# 846-XXXXX_SCH_NEO-M9N_MODULE_2_RECEIVER.net
KiCad netlist of a schematic drawn in Altium Designer
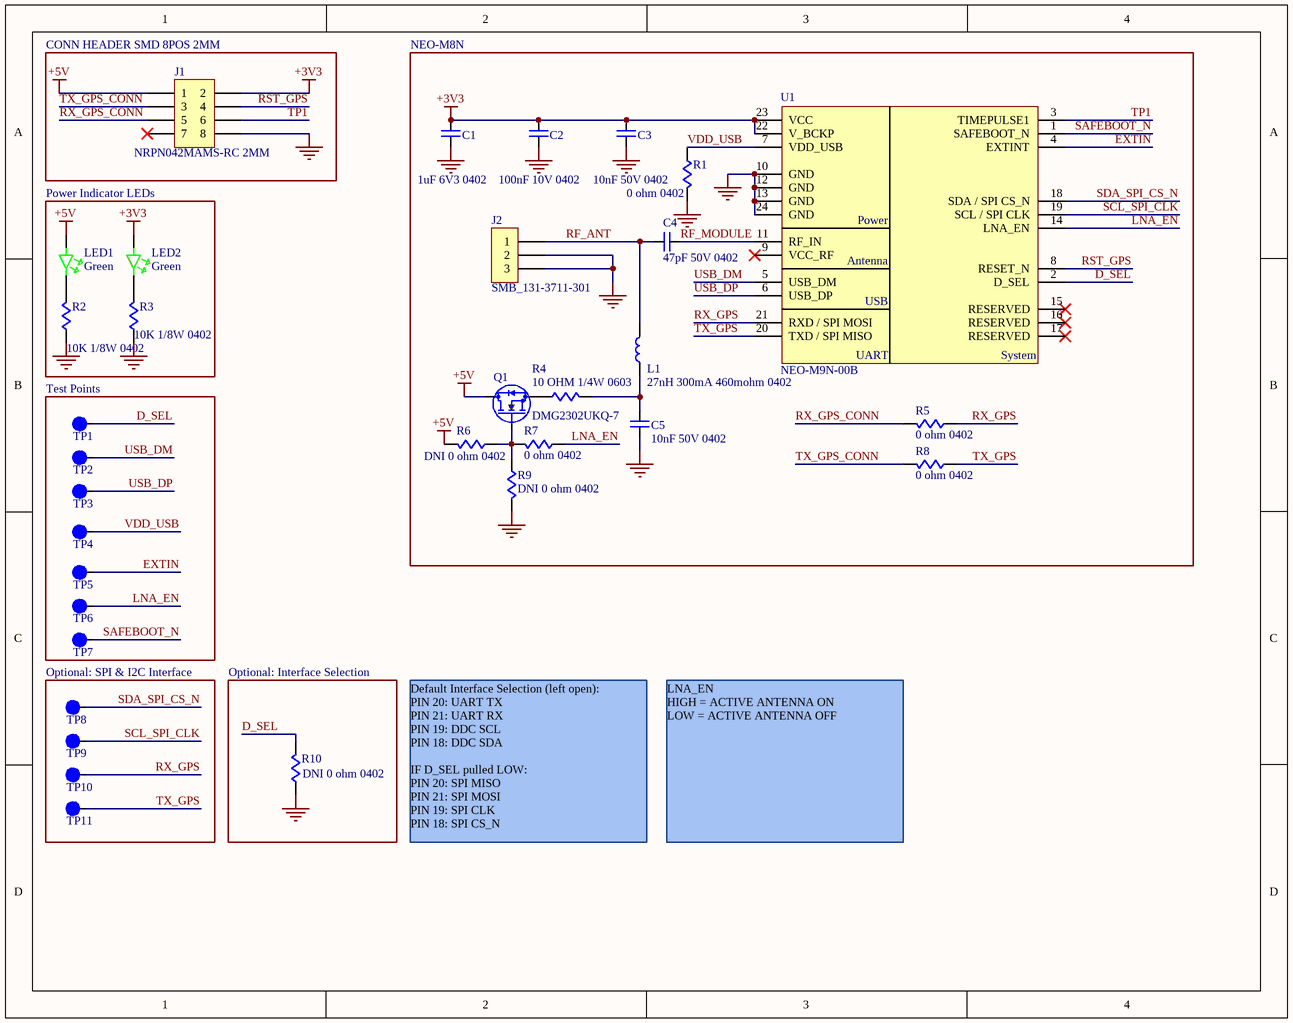
[diagram p0: 846-XXXXX_SCH_NEO-M9N_MODULE_2_RECEIVER.SchDoc]

(export (version "E")
  (design (tool "Eeschema 10.0.6"))
  (components
    (comp (ref "C1")
      (value "1uF 6V3 0402")
      (footprint "c0402")
      (description "0402 1 uF 6.3 V ±10% Tolerance X7R Multilayer Ceramic Capacitor")
      (fields
        (field (name "MANUFACTURER") "Murata")
        (field (name "MANUFACTURER PART NUMBER") "GRM155R70J105KA12J")
      )
      (libsource (lib "MyLibrary") (part "CAP CER 1UF 6.3V X7R 0402"))
    )
    (comp (ref "C2")
      (value "100nF 10V 0402")
      (footprint "c0402")
      (description "CL05 Series 0.1 uF 10 V ±10 % Tolerance X7R SMT Multilayer Ceramic Capacitor")
      (fields
        (field (name "MANUFACTURER") "Samsung")
        (field (name "MANUFACTURER PART NUMBER") "CL05B104KP5NNNC")
      )
      (libsource (lib "MyLibrary") (part "CAP CER 0.1UF 10V X7R 0402"))
    )
    (comp (ref "C3")
      (value "10nF 50V 0402")
      (footprint "c0402")
      (description "CAP CER 10000PF 50V X7R 0402")
      (fields
        (field (name "MANUFACTURER") "Murata")
        (field (name "MANUFACTURER PART NUMBER") "GCM155R71H103KA55D")
      )
      (libsource (lib "MyLibrary") (part "CAP CER 10000PF 50V X7R 0402"))
    )
    (comp (ref "C4")
      (value "47pF 50V 0402")
      (footprint "c0402")
      (description "0402 47 pF 50 V ±5 % Tolerance NP0 SMT Multilayer Ceramic Capacitor")
      (fields
        (field (name "MANUFACTURER") "Yageo")
        (field (name "MANUFACTURER PART NUMBER") "CC0402JRNPO9BN470")
      )
      (libsource (lib "MyLibrary") (part "CAP CER 47PF 50V C0G/NPO 0402"))
    )
    (comp (ref "C5")
      (value "10nF 50V 0402")
      (footprint "c0402")
      (description "CAP CER 10000PF 50V X7R 0402")
      (fields
        (field (name "MANUFACTURER") "Murata")
        (field (name "MANUFACTURER PART NUMBER") "GCM155R71H103KA55D")
      )
      (libsource (lib "MyLibrary") (part "CAP CER 10000PF 50V X7R 0402"))
    )
    (comp (ref "J1")
      (value "NRPN042MAMS-RC 2MM")
      (footprint "CONN_NRPN042MAMS-RC")
      (description "Dual Row 8 Position 2 mm Pitch Surface Mount Header")
      (fields
        (field (name "MANUFACTURER") "Sullins")
        (field (name "MANUFACTURER PART NUMBER") "NRPN042MAMS-RC")
      )
      (libsource (lib "MyLibrary") (part "CONN_NRPN042MAMS-RC"))
    )
    (comp (ref "J2")
      (value "SMB_131-3711-301")
      (footprint "CONN_131-3711-301")
      (description "Rf Coaxial Board Mount Connector")
      (fields
        (field (name "MANUFACTURER") "Bel Cinch")
        (field (name "MANUFACTURER PART NUMBER") "131-3711-301")
      )
      (libsource (lib "MyLibrary") (part "CONN_131-3711-301"))
    )
    (comp (ref "L1")
      (value "27nH 300mA 460mohm 0402")
      (footprint "L0402")
      (description "Inductor RF Chip Multi-Layer 27nH 5% 100MHz 8Q-Factor Air 300mA 460mOhm DCR 0402 Paper T/R")
      (fields
        (field (name "MANUFACTURER") "Murata")
        (field (name "MANUFACTURER PART NUMBER") "LQG15HS27NJ02D")
      )
      (libsource (lib "MyLibrary") (part "FIXED IND 27NH 350MA 460MOHM SMD"))
    )
    (comp (ref "LED1")
      (value "Green")
      (footprint "led0603")
      (description "LED High-Power Uni-Color Green 574nm 2-Pin Chip LED T/R")
      (fields
        (field (name "MANUFACTURER") "Vishay Lite-On")
        (field (name "MANUFACTURER PART NUMBER") "LTST-C190KGKT")
      )
      (libsource (lib "MyLibrary") (part "LED GREEN CLEAR CHIP SMD"))
    )
    (comp (ref "LED2")
      (value "Green")
      (footprint "led0603")
      (description "LED High-Power Uni-Color Green 574nm 2-Pin Chip LED T/R")
      (fields
        (field (name "MANUFACTURER") "Vishay Lite-On")
        (field (name "MANUFACTURER PART NUMBER") "LTST-C190KGKT")
      )
      (libsource (lib "MyLibrary") (part "LED GREEN CLEAR CHIP SMD"))
    )
    (comp (ref "Q1")
      (value "DMG2302UKQ-7")
      (footprint "SOT23")
      (description "N-Channel 20 V 2.8A (Ta) 660mW (Ta) Surface Mount SOT-23-3")
      (fields
        (field (name "MANUFACTURER") "Diodes")
        (field (name "COPYRIGHT") "Copyright (C) 2022 Ultra Librarian. All rights reserved.")
      )
      (libsource (lib "MyLibrary") (part "DMG2302UKQ-7"))
    )
    (comp (ref "R1")
      (value "0 ohm 0402")
      (footprint "r0402")
      (description "RES SMD 0 OHM JUMPER 1/16W 0402")
      (fields
        (field (name "MANUFACTURER") "Yageo")
        (field (name "MANUFACTURER PART NUMBER") "RC0402JR-070RL")
      )
      (libsource (lib "MyLibrary") (part "RES 0 OHM JUMPER 1/16W 0402"))
    )
    (comp (ref "R2")
      (value "10K 1/8W 0402")
      (footprint "r0402")
      (description "Res Thick Film 0402 10K Ohm 1% 0.125W(1/8W) ±100ppm/°C Pad SMD T/R")
      (fields
        (field (name "MANUFACTURER") "TE Connectivity")
        (field (name "MANUFACTURER PART NUMBER") "CRGP0402F10K")
      )
      (libsource (lib "MyLibrary") (part "RES 10K OHM 1% 1/8W 0402"))
    )
    (comp (ref "R3")
      (value "10K 1/8W 0402")
      (footprint "r0402")
      (description "Res Thick Film 0402 10K Ohm 1% 0.125W(1/8W) ±100ppm/°C Pad SMD T/R")
      (fields
        (field (name "MANUFACTURER") "TE Connectivity")
        (field (name "MANUFACTURER PART NUMBER") "CRGP0402F10K")
      )
      (libsource (lib "MyLibrary") (part "RES 10K OHM 1% 1/8W 0402"))
    )
    (comp (ref "R4")
      (value "10 OHM 1/4W 0603")
      (footprint "r0603")
      (description "Res Surge Chip Thick Film 0603 10 Ohm 1% 1/4W ±200ppm/°C Molded Paper T/R")
      (fields
        (field (name "MANUFACTURER") "Yageo")
        (field (name "MANUFACTURER PART NUMBER") "SR0603FR-7T10RL")
      )
      (libsource (lib "MyLibrary") (part "RES SMD 10 OHM 1% 1/4W 0603"))
    )
    (comp (ref "R5")
      (value "0 ohm 0402")
      (footprint "r0402")
      (description "RES SMD 0 OHM JUMPER 1/16W 0402")
      (fields
        (field (name "MANUFACTURER") "Yageo")
        (field (name "MANUFACTURER PART NUMBER") "RC0402JR-070RL")
      )
      (libsource (lib "MyLibrary") (part "RES 0 OHM JUMPER 1/16W 0402"))
    )
    (comp (ref "R6")
      (value "DNI 0 ohm 0402")
      (footprint "r0402")
      (description "RES SMD 0 OHM JUMPER 1/16W 0402")
      (fields
        (field (name "MANUFACTURER") "Yageo")
        (field (name "MANUFACTURER PART NUMBER") "RC0402JR-070RL")
      )
      (libsource (lib "MyLibrary") (part "RES 0 OHM JUMPER 1/16W 0402"))
    )
    (comp (ref "R7")
      (value "0 ohm 0402")
      (footprint "r0402")
      (description "RES SMD 0 OHM JUMPER 1/16W 0402")
      (fields
        (field (name "MANUFACTURER") "Yageo")
        (field (name "MANUFACTURER PART NUMBER") "RC0402JR-070RL")
      )
      (libsource (lib "MyLibrary") (part "RES 0 OHM JUMPER 1/16W 0402"))
    )
    (comp (ref "R8")
      (value "0 ohm 0402")
      (footprint "r0402")
      (description "RES SMD 0 OHM JUMPER 1/16W 0402")
      (fields
        (field (name "MANUFACTURER") "Yageo")
        (field (name "MANUFACTURER PART NUMBER") "RC0402JR-070RL")
      )
      (libsource (lib "MyLibrary") (part "RES 0 OHM JUMPER 1/16W 0402"))
    )
    (comp (ref "R9")
      (value "DNI 0 ohm 0402")
      (footprint "r0402")
      (description "RES SMD 0 OHM JUMPER 1/16W 0402")
      (fields
        (field (name "MANUFACTURER") "Yageo")
        (field (name "MANUFACTURER PART NUMBER") "RC0402JR-070RL")
      )
      (libsource (lib "MyLibrary") (part "RES 0 OHM JUMPER 1/16W 0402"))
    )
    (comp (ref "R10")
      (value "DNI 0 ohm 0402")
      (footprint "r0402")
      (description "RES SMD 0 OHM JUMPER 1/16W 0402")
      (fields
        (field (name "MANUFACTURER") "Yageo")
        (field (name "MANUFACTURER PART NUMBER") "RC0402JR-070RL")
      )
      (libsource (lib "MyLibrary") (part "RES 0 OHM JUMPER 1/16W 0402"))
    )
    (comp (ref "TP1")
      (value "1MM")
      (footprint "TP1MM")
      (description "Test Point 1MM diameter")
      (libsource (lib "MyLibrary") (part "TP_1MM"))
    )
    (comp (ref "TP2")
      (value "1MM")
      (footprint "TP1MM")
      (description "Test Point 1MM diameter")
      (libsource (lib "MyLibrary") (part "TP_1MM"))
    )
    (comp (ref "TP3")
      (value "1MM")
      (footprint "TP1MM")
      (description "Test Point 1MM diameter")
      (libsource (lib "MyLibrary") (part "TP_1MM"))
    )
    (comp (ref "TP4")
      (value "1MM")
      (footprint "TP1MM")
      (description "Test Point 1MM diameter")
      (libsource (lib "MyLibrary") (part "TP_1MM"))
    )
    (comp (ref "TP5")
      (value "1MM")
      (footprint "TP1MM")
      (description "Test Point 1MM diameter")
      (libsource (lib "MyLibrary") (part "TP_1MM"))
    )
    (comp (ref "TP6")
      (value "1MM")
      (footprint "TP1MM")
      (description "Test Point 1MM diameter")
      (libsource (lib "MyLibrary") (part "TP_1MM"))
    )
    (comp (ref "TP7")
      (value "1MM")
      (footprint "TP1MM")
      (description "Test Point 1MM diameter")
      (libsource (lib "MyLibrary") (part "TP_1MM"))
    )
    (comp (ref "TP8")
      (value "1MM")
      (footprint "TP1MM")
      (description "Test Point 1MM diameter")
      (libsource (lib "MyLibrary") (part "TP_1MM"))
    )
    (comp (ref "TP9")
      (value "1MM")
      (footprint "TP1MM")
      (description "Test Point 1MM diameter")
      (libsource (lib "MyLibrary") (part "TP_1MM"))
    )
    (comp (ref "TP10")
      (value "1MM")
      (footprint "TP1MM")
      (description "Test Point 1MM diameter")
      (libsource (lib "MyLibrary") (part "TP_1MM"))
    )
    (comp (ref "TP11")
      (value "1MM")
      (footprint "TP1MM")
      (description "Test Point 1MM diameter")
      (libsource (lib "MyLibrary") (part "TP_1MM"))
    )
    (comp (ref "U1")
      (value "NEO-M9N-00B")
      (footprint "IC_NEO-M9N")
      (description "GNSS module, Flash, TCXO, SAW, LNA, LCC, 12x16 mm Professional Grade")
      (fields (field (name "MANUFACTURER") "u-blox"))
      (libsource (lib "MyLibrary") (part "IC NEO-M9N-00B"))
    )
  )
  (nets
    (net (code "1") (name "+3V3") (class "Default")
      (node (ref "C1") (pin "2") (pinfunction "2_2") (pintype "passive"))
      (node (ref "C2") (pin "2") (pinfunction "2_2") (pintype "passive"))
      (node (ref "C3") (pin "2") (pinfunction "2_2") (pintype "passive"))
      (node (ref "J1") (pin "2") (pinfunction "2_2") (pintype "passive"))
      (node (ref "LED2") (pin "1") (pinfunction "1_1") (pintype "passive"))
      (node (ref "U1") (pin "22") (pinfunction "V_BCKP_22") (pintype "passive"))
      (node (ref "U1") (pin "23") (pinfunction "VCC_23") (pintype "passive"))
    )
    (net (code "2") (name "+5V") (class "Default")
      (node (ref "J1") (pin "1") (pinfunction "1_1") (pintype "passive"))
      (node (ref "LED1") (pin "1") (pinfunction "1_1") (pintype "passive"))
      (node (ref "Q1") (pin "2") (pinfunction "D_2") (pintype "passive"))
      (node (ref "R6") (pin "2") (pinfunction "2_2") (pintype "passive"))
    )
    (net (code "3") (name "/D_SEL") (class "Default")
      (node (ref "R10") (pin "2") (pinfunction "2_2") (pintype "passive"))
      (node (ref "TP1") (pin "1") (pinfunction "1_1") (pintype "passive"))
      (node (ref "U1") (pin "2") (pinfunction "D_SEL_2") (pintype "passive"))
    )
    (net (code "4") (name "/EXTIN") (class "Default")
      (node (ref "TP5") (pin "1") (pinfunction "1_1") (pintype "passive"))
      (node (ref "U1") (pin "4") (pinfunction "EXTINT_4") (pintype "passive"))
    )
    (net (code "5") (name "/LNA_EN") (class "Default")
      (node (ref "R7") (pin "1") (pinfunction "1_1") (pintype "passive"))
      (node (ref "TP6") (pin "1") (pinfunction "1_1") (pintype "passive"))
      (node (ref "U1") (pin "14") (pinfunction "LNA_EN_14") (pintype "passive"))
    )
    (net (code "6") (name "/RF_ANT") (class "Default")
      (node (ref "C4") (pin "1") (pinfunction "1_1") (pintype "passive"))
      (node (ref "J2") (pin "1") (pinfunction "1_1") (pintype "passive"))
      (node (ref "L1") (pin "2") (pinfunction "2_2") (pintype "passive"))
    )
    (net (code "7") (name "/RF_MODULE") (class "Default")
      (node (ref "C4") (pin "2") (pinfunction "2_2") (pintype "passive"))
      (node (ref "U1") (pin "11") (pinfunction "RF_IN_11") (pintype "passive"))
    )
    (net (code "8") (name "/RST_GPS") (class "Default")
      (node (ref "J1") (pin "4") (pinfunction "4_4") (pintype "passive"))
      (node (ref "U1") (pin "8") (pinfunction "RESET_N_8") (pintype "passive"))
    )
    (net (code "9") (name "/RX_GPS") (class "Default")
      (node (ref "R5") (pin "1") (pinfunction "1_1") (pintype "passive"))
      (node (ref "TP10") (pin "1") (pinfunction "1_1") (pintype "passive"))
      (node (ref "U1") (pin "21") (pinfunction "RXD_/_SPI_MOSI_21") (pintype "passive"))
    )
    (net (code "10") (name "/RX_GPS_CONN") (class "Default")
      (node (ref "J1") (pin "5") (pinfunction "5_5") (pintype "passive"))
      (node (ref "R5") (pin "2") (pinfunction "2_2") (pintype "passive"))
    )
    (net (code "11") (name "/SAFEBOOT_N") (class "Default")
      (node (ref "TP7") (pin "1") (pinfunction "1_1") (pintype "passive"))
      (node (ref "U1") (pin "1") (pinfunction "SAFEBOOT_N_1") (pintype "passive"))
    )
    (net (code "12") (name "/SCL_SPI_CLK") (class "Default")
      (node (ref "TP9") (pin "1") (pinfunction "1_1") (pintype "passive"))
      (node (ref "U1") (pin "19") (pinfunction "SCL_/_SPI_CLK_19") (pintype "passive"))
    )
    (net (code "13") (name "/SDA_SPI_CS_N") (class "Default")
      (node (ref "TP8") (pin "1") (pinfunction "1_1") (pintype "passive"))
      (node (ref "U1") (pin "18") (pinfunction "SDA_/_SPI_CS_N_18") (pintype "passive"))
    )
    (net (code "14") (name "/TP1") (class "Default")
      (node (ref "J1") (pin "6") (pinfunction "6_6") (pintype "passive"))
      (node (ref "U1") (pin "3") (pinfunction "TIMEPULSE1_3") (pintype "passive"))
    )
    (net (code "15") (name "/TX_GPS") (class "Default")
      (node (ref "R8") (pin "1") (pinfunction "1_1") (pintype "passive"))
      (node (ref "TP11") (pin "1") (pinfunction "1_1") (pintype "passive"))
      (node (ref "U1") (pin "20") (pinfunction "TXD_/_SPI_MISO_20") (pintype "passive"))
    )
    (net (code "16") (name "/TX_GPS_CONN") (class "Default")
      (node (ref "J1") (pin "3") (pinfunction "3_3") (pintype "passive"))
      (node (ref "R8") (pin "2") (pinfunction "2_2") (pintype "passive"))
    )
    (net (code "17") (name "/USB_DM") (class "Default")
      (node (ref "TP2") (pin "1") (pinfunction "1_1") (pintype "passive"))
      (node (ref "U1") (pin "5") (pinfunction "USB_DM_5") (pintype "passive"))
    )
    (net (code "18") (name "/USB_DP") (class "Default")
      (node (ref "TP3") (pin "1") (pinfunction "1_1") (pintype "passive"))
      (node (ref "U1") (pin "6") (pinfunction "USB_DP_6") (pintype "passive"))
    )
    (net (code "19") (name "/VDD_USB") (class "Default")
      (node (ref "R1") (pin "1") (pinfunction "1_1") (pintype "passive"))
      (node (ref "TP4") (pin "1") (pinfunction "1_1") (pintype "passive"))
      (node (ref "U1") (pin "7") (pinfunction "VDD_USB_7") (pintype "passive"))
    )
    (net (code "20") (name "GND") (class "Default")
      (node (ref "C1") (pin "1") (pinfunction "1_1") (pintype "passive"))
      (node (ref "C2") (pin "1") (pinfunction "1_1") (pintype "passive"))
      (node (ref "C3") (pin "1") (pinfunction "1_1") (pintype "passive"))
      (node (ref "C5") (pin "1") (pinfunction "1_1") (pintype "passive"))
      (node (ref "J1") (pin "8") (pinfunction "8_8") (pintype "passive"))
      (node (ref "J2") (pin "2") (pinfunction "2_2") (pintype "passive"))
      (node (ref "J2") (pin "3") (pinfunction "3_3") (pintype "passive"))
      (node (ref "R1") (pin "2") (pinfunction "2_2") (pintype "passive"))
      (node (ref "R10") (pin "1") (pinfunction "1_1") (pintype "passive"))
      (node (ref "R2") (pin "1") (pinfunction "1_1") (pintype "passive"))
      (node (ref "R3") (pin "1") (pinfunction "1_1") (pintype "passive"))
      (node (ref "R9") (pin "2") (pinfunction "2_2") (pintype "passive"))
      (node (ref "U1") (pin "10") (pinfunction "GND_10") (pintype "passive"))
      (node (ref "U1") (pin "12") (pinfunction "GND_12") (pintype "passive"))
      (node (ref "U1") (pin "13") (pinfunction "GND_13") (pintype "passive"))
      (node (ref "U1") (pin "24") (pinfunction "GND_24") (pintype "passive"))
    )
    (net (code "21") (name "Net-(C5-Pad2)") (class "Default")
      (node (ref "C5") (pin "2") (pinfunction "2_2") (pintype "passive"))
      (node (ref "L1") (pin "1") (pinfunction "1_1") (pintype "passive"))
      (node (ref "R4") (pin "2") (pinfunction "2_2") (pintype "passive"))
    )
    (net (code "22") (name "Net-(LED1-Pad2)") (class "Default")
      (node (ref "LED1") (pin "2") (pinfunction "2_2") (pintype "passive"))
      (node (ref "R2") (pin "2") (pinfunction "2_2") (pintype "passive"))
    )
    (net (code "23") (name "Net-(LED2-Pad2)") (class "Default")
      (node (ref "LED2") (pin "2") (pinfunction "2_2") (pintype "passive"))
      (node (ref "R3") (pin "2") (pinfunction "2_2") (pintype "passive"))
    )
    (net (code "24") (name "Net-(Q1-G)") (class "Default")
      (node (ref "Q1") (pin "1") (pinfunction "G_1") (pintype "passive"))
      (node (ref "R6") (pin "1") (pinfunction "1_1") (pintype "passive"))
      (node (ref "R7") (pin "2") (pinfunction "2_2") (pintype "passive"))
      (node (ref "R9") (pin "1") (pinfunction "1_1") (pintype "passive"))
    )
    (net (code "25") (name "Net-(Q1-S)") (class "Default")
      (node (ref "Q1") (pin "3") (pinfunction "S_3") (pintype "passive"))
      (node (ref "R4") (pin "1") (pinfunction "1_1") (pintype "passive"))
    )
    (net (code "26") (name "unconnected-(J1-Pad7)") (class "Default")
      (node (ref "J1") (pin "7") (pinfunction "7_7") (pintype "passive+no_connect"))
    )
    (net (code "27") (name "unconnected-(U1-RESERVED-Pad15)") (class "Default")
      (node (ref "U1") (pin "15") (pinfunction "RESERVED_15") (pintype "passive+no_connect"))
    )
    (net (code "28") (name "unconnected-(U1-RESERVED-Pad16)") (class "Default")
      (node (ref "U1") (pin "16") (pinfunction "RESERVED_16") (pintype "passive+no_connect"))
    )
    (net (code "29") (name "unconnected-(U1-RESERVED-Pad17)") (class "Default")
      (node (ref "U1") (pin "17") (pinfunction "RESERVED_17") (pintype "passive+no_connect"))
    )
    (net (code "30") (name "unconnected-(U1-VCC_RF-Pad9)") (class "Default")
      (node (ref "U1") (pin "9") (pinfunction "VCC_RF_9") (pintype "passive+no_connect"))
    )
  )
)
